# CPU_-_DDR3.net
KiCad netlist of a schematic drawn in Altium Designer
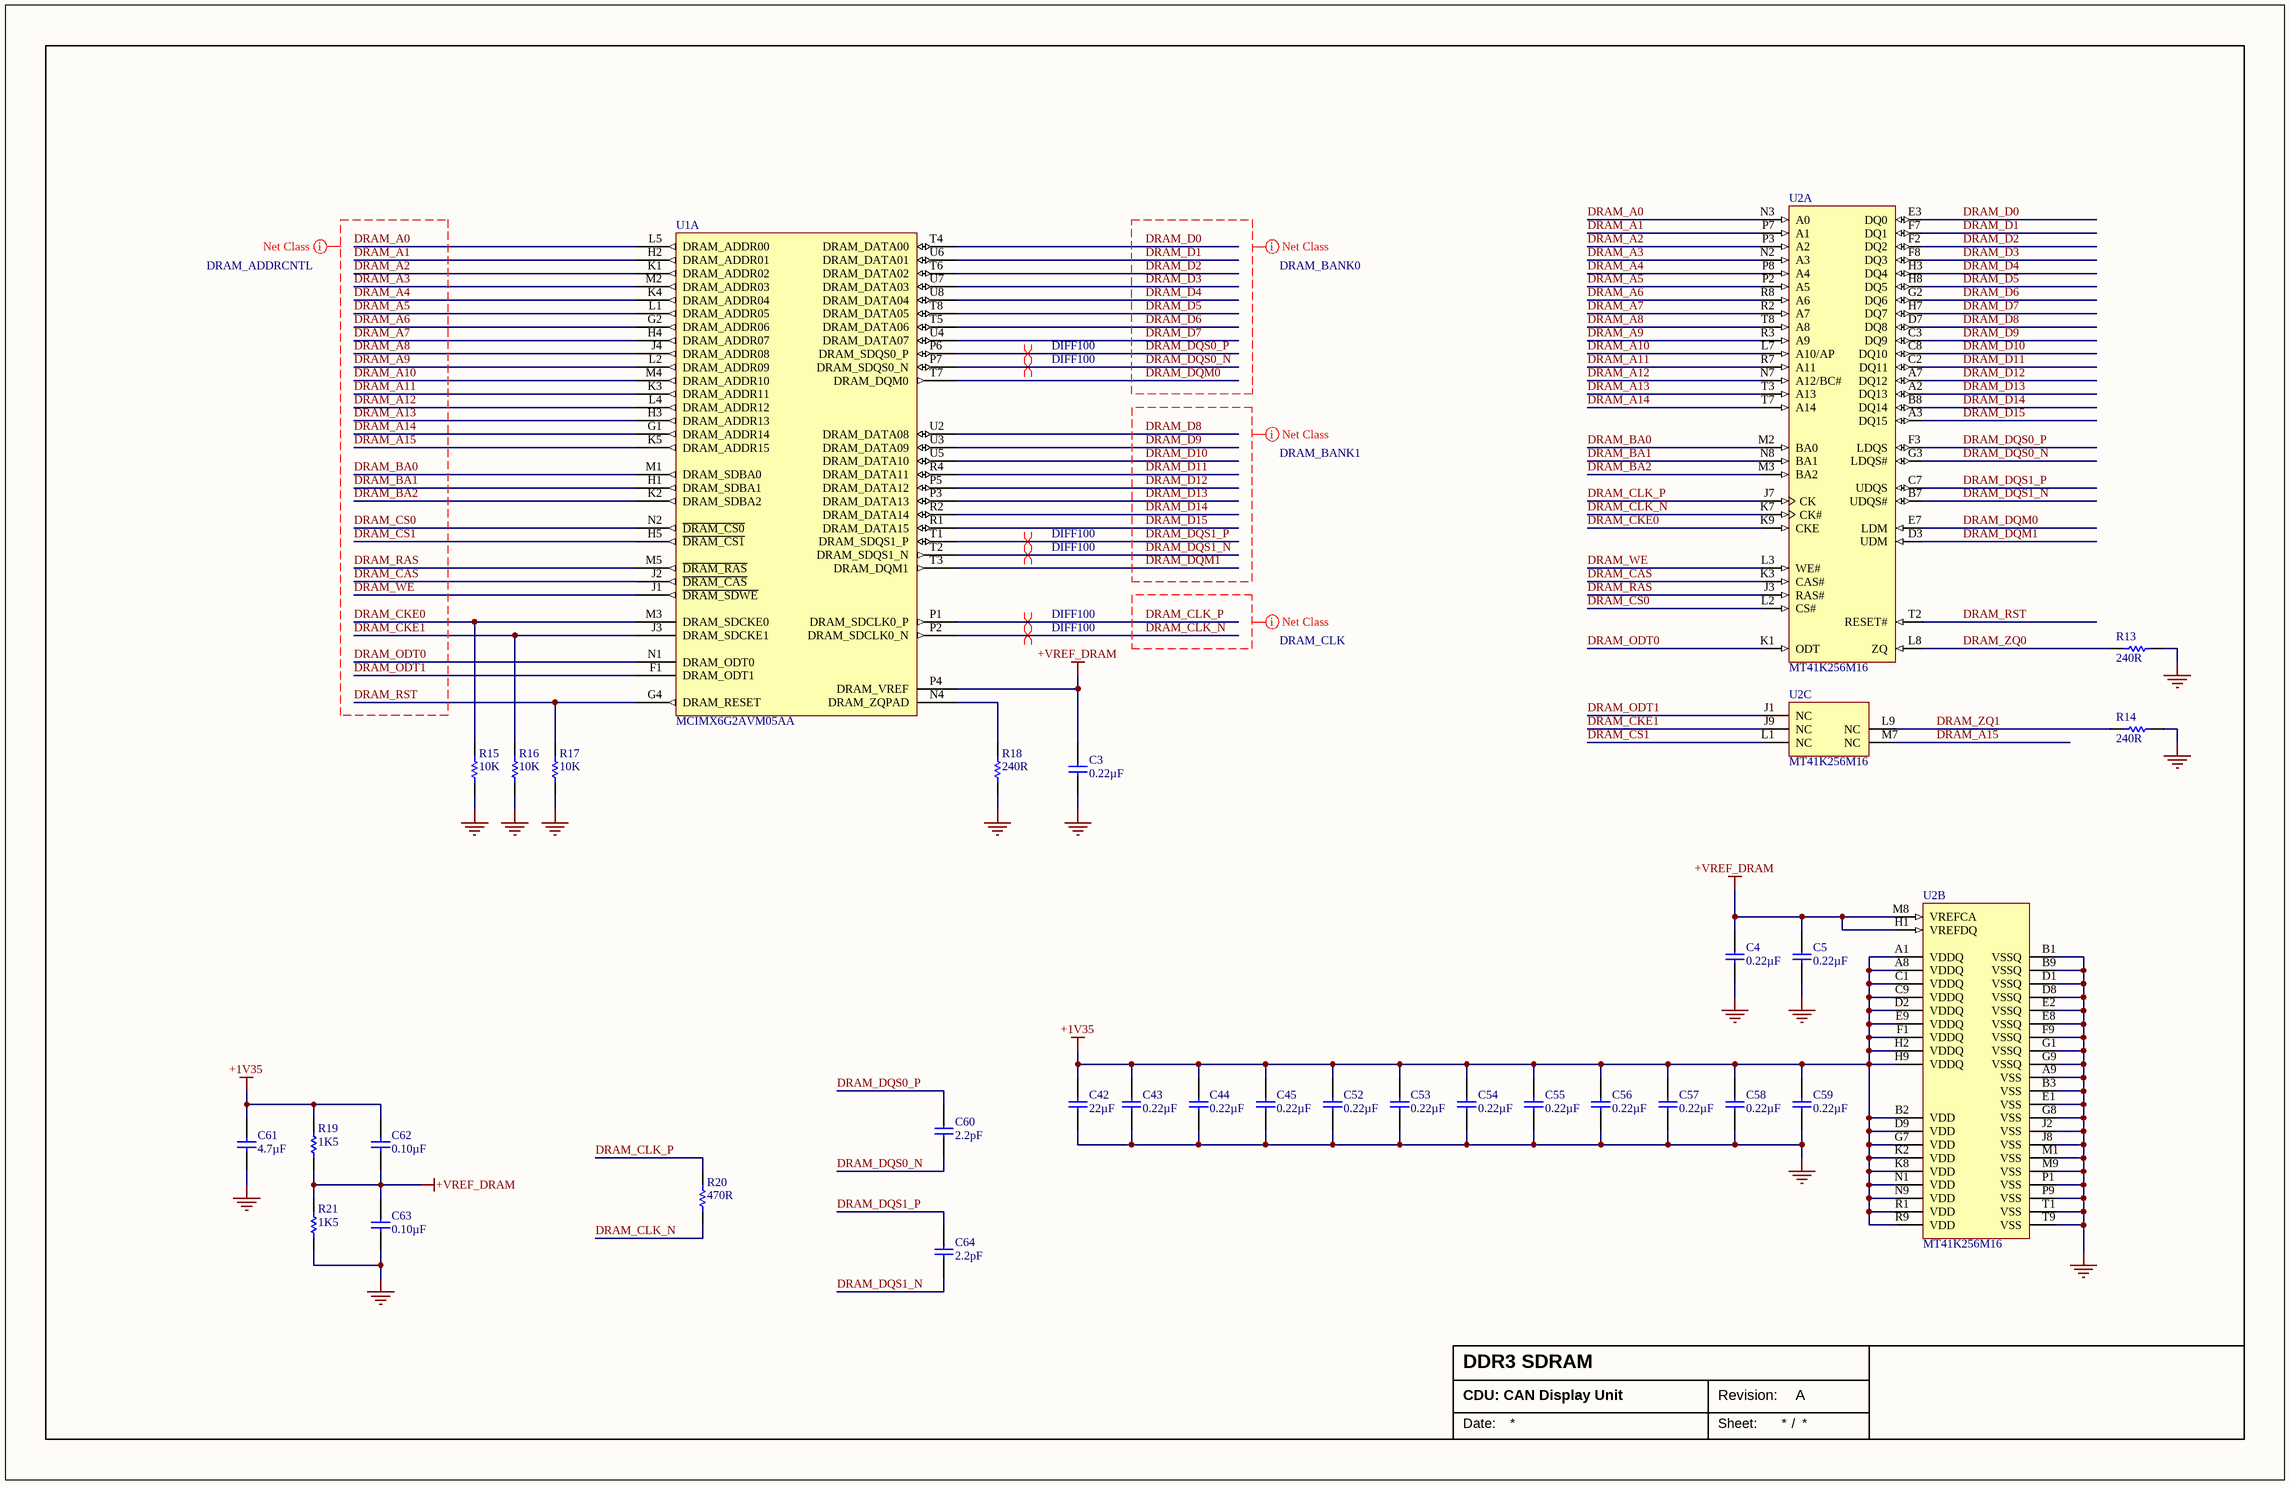
[diagram p0: CPU - DDR3.SchDoc]

(export (version "E")
  (design (tool "Eeschema 10.0.6"))
  (components
    (comp (ref "C3")
      (value "0.22µF")
      (footprint "CAP-0402-M")
      (fields
        (field (name "PART NUMBER") "CC0402KRX7R7BB224")
        (field (name "TOLERANCE") "±10%")
        (field (name "VOLTAGE") "16V")
      )
      (libsource (lib "Capacitors") (part "Capacitor"))
    )
    (comp (ref "C4")
      (value "0.22µF")
      (footprint "CAP-0402-M")
      (fields
        (field (name "PART NUMBER") "CC0402KRX7R7BB224")
        (field (name "TOLERANCE") "±10%")
        (field (name "VOLTAGE") "16V")
      )
      (libsource (lib "Capacitors") (part "Capacitor"))
    )
    (comp (ref "C5")
      (value "0.22µF")
      (footprint "CAP-0402-M")
      (fields
        (field (name "PART NUMBER") "CC0402KRX7R7BB224")
        (field (name "TOLERANCE") "±10%")
        (field (name "VOLTAGE") "16V")
      )
      (libsource (lib "Capacitors") (part "Capacitor"))
    )
    (comp (ref "C42")
      (value "22µF")
      (footprint "CAP-0603-M")
      (fields
        (field (name "PART NUMBER") "CC0603MRX5R6BB226")
        (field (name "TOLERANCE") "±20%")
        (field (name "VOLTAGE") "10V")
      )
      (libsource (lib "Capacitors") (part "Capacitor"))
    )
    (comp (ref "C43")
      (value "0.22µF")
      (footprint "CAP-0402-M")
      (fields
        (field (name "PART NUMBER") "CC0402KRX7R7BB224")
        (field (name "TOLERANCE") "±10%")
        (field (name "VOLTAGE") "16V")
      )
      (libsource (lib "Capacitors") (part "Capacitor"))
    )
    (comp (ref "C44")
      (value "0.22µF")
      (footprint "CAP-0402-M")
      (fields
        (field (name "PART NUMBER") "CC0402KRX7R7BB224")
        (field (name "TOLERANCE") "±10%")
        (field (name "VOLTAGE") "16V")
      )
      (libsource (lib "Capacitors") (part "Capacitor"))
    )
    (comp (ref "C45")
      (value "0.22µF")
      (footprint "CAP-0402-M")
      (fields
        (field (name "PART NUMBER") "CC0402KRX7R7BB224")
        (field (name "TOLERANCE") "±10%")
        (field (name "VOLTAGE") "16V")
      )
      (libsource (lib "Capacitors") (part "Capacitor"))
    )
    (comp (ref "C52")
      (value "0.22µF")
      (footprint "CAP-0402-M")
      (fields
        (field (name "PART NUMBER") "CC0402KRX7R7BB224")
        (field (name "TOLERANCE") "±10%")
        (field (name "VOLTAGE") "16V")
      )
      (libsource (lib "Capacitors") (part "Capacitor"))
    )
    (comp (ref "C53")
      (value "0.22µF")
      (footprint "CAP-0402-M")
      (fields
        (field (name "PART NUMBER") "CC0402KRX7R7BB224")
        (field (name "TOLERANCE") "±10%")
        (field (name "VOLTAGE") "16V")
      )
      (libsource (lib "Capacitors") (part "Capacitor"))
    )
    (comp (ref "C54")
      (value "0.22µF")
      (footprint "CAP-0402-M")
      (fields
        (field (name "PART NUMBER") "CC0402KRX7R7BB224")
        (field (name "TOLERANCE") "±10%")
        (field (name "VOLTAGE") "16V")
      )
      (libsource (lib "Capacitors") (part "Capacitor"))
    )
    (comp (ref "C55")
      (value "0.22µF")
      (footprint "CAP-0402-M")
      (fields
        (field (name "PART NUMBER") "CC0402KRX7R7BB224")
        (field (name "TOLERANCE") "±10%")
        (field (name "VOLTAGE") "16V")
      )
      (libsource (lib "Capacitors") (part "Capacitor"))
    )
    (comp (ref "C56")
      (value "0.22µF")
      (footprint "CAP-0402-M")
      (fields
        (field (name "PART NUMBER") "CC0402KRX7R7BB224")
        (field (name "TOLERANCE") "±10%")
        (field (name "VOLTAGE") "16V")
      )
      (libsource (lib "Capacitors") (part "Capacitor"))
    )
    (comp (ref "C57")
      (value "0.22µF")
      (footprint "CAP-0402-M")
      (fields
        (field (name "PART NUMBER") "CC0402KRX7R7BB224")
        (field (name "TOLERANCE") "±10%")
        (field (name "VOLTAGE") "16V")
      )
      (libsource (lib "Capacitors") (part "Capacitor"))
    )
    (comp (ref "C58")
      (value "0.22µF")
      (footprint "CAP-0402-M")
      (fields
        (field (name "PART NUMBER") "CC0402KRX7R7BB224")
        (field (name "TOLERANCE") "±10%")
        (field (name "VOLTAGE") "16V")
      )
      (libsource (lib "Capacitors") (part "Capacitor"))
    )
    (comp (ref "C59")
      (value "0.22µF")
      (footprint "CAP-0402-M")
      (fields
        (field (name "PART NUMBER") "CC0402KRX7R7BB224")
        (field (name "TOLERANCE") "±10%")
        (field (name "VOLTAGE") "16V")
      )
      (libsource (lib "Capacitors") (part "Capacitor"))
    )
    (comp (ref "C60")
      (value "2.2pF")
      (footprint "CAP-0402-M")
      (fields
        (field (name "PART NUMBER") "CC0402BRNPO9BN2R2")
        (field (name "TOLERANCE") "±0.1pF")
        (field (name "VOLTAGE") "50V")
      )
      (libsource (lib "Capacitors") (part "Capacitor"))
    )
    (comp (ref "C61")
      (value "4.7µF")
      (footprint "CAP-0603-M")
      (fields
        (field (name "PART NUMBER") "CC0603KRX5R6BB475")
        (field (name "TOLERANCE") "±10%")
        (field (name "VOLTAGE") "10V")
      )
      (libsource (lib "Capacitors") (part "Capacitor"))
    )
    (comp (ref "C62")
      (value "0.10µF")
      (footprint "CAP-0402-M")
      (fields
        (field (name "PART NUMBER") "CC0402KRX7R8BB104")
        (field (name "TOLERANCE") "±10%")
        (field (name "VOLTAGE") "25V")
      )
      (libsource (lib "Capacitors") (part "Capacitor"))
    )
    (comp (ref "C63")
      (value "0.10µF")
      (footprint "CAP-0402-M")
      (fields
        (field (name "PART NUMBER") "CC0402KRX7R8BB104")
        (field (name "TOLERANCE") "±10%")
        (field (name "VOLTAGE") "25V")
      )
      (libsource (lib "Capacitors") (part "Capacitor"))
    )
    (comp (ref "C64")
      (value "2.2pF")
      (footprint "CAP-0402-M")
      (fields
        (field (name "PART NUMBER") "CC0402BRNPO9BN2R2")
        (field (name "TOLERANCE") "±0.1pF")
        (field (name "VOLTAGE") "50V")
      )
      (libsource (lib "Capacitors") (part "Capacitor"))
    )
    (comp (ref "R13")
      (value "240R")
      (footprint "RES-0402-M")
      (fields
        (field (name "PART NUMBER") "RC0402FR-07240RL")
        (field (name "TOLERANCE") "1%")
        (field (name "POWER") "1/16W")
      )
      (libsource (lib "Resistors") (part "Resistor"))
    )
    (comp (ref "R14")
      (value "240R")
      (footprint "RES-0402-M")
      (fields
        (field (name "PART NUMBER") "RC0402FR-07240RL")
        (field (name "TOLERANCE") "1%")
        (field (name "POWER") "1/16W")
      )
      (libsource (lib "Resistors") (part "Resistor"))
    )
    (comp (ref "R15")
      (value "10K")
      (footprint "RES-0603-M")
      (fields
        (field (name "PART NUMBER") "RC0603FR-0710KL")
        (field (name "TOLERANCE") "1%")
        (field (name "POWER") "1/10 W")
      )
      (libsource (lib "Resistors") (part "Resistor"))
    )
    (comp (ref "R16")
      (value "10K")
      (footprint "RES-0603-M")
      (fields
        (field (name "PART NUMBER") "RC0603FR-0710KL")
        (field (name "TOLERANCE") "1%")
        (field (name "POWER") "1/10 W")
      )
      (libsource (lib "Resistors") (part "Resistor"))
    )
    (comp (ref "R17")
      (value "10K")
      (footprint "RES-0603-M")
      (fields
        (field (name "PART NUMBER") "RC0603FR-0710KL")
        (field (name "TOLERANCE") "1%")
        (field (name "POWER") "1/10 W")
      )
      (libsource (lib "Resistors") (part "Resistor"))
    )
    (comp (ref "R18")
      (value "240R")
      (footprint "RES-0402-M")
      (fields
        (field (name "PART NUMBER") "RC0402FR-07240RL")
        (field (name "TOLERANCE") "1%")
        (field (name "POWER") "1/16W")
      )
      (libsource (lib "Resistors") (part "Resistor"))
    )
    (comp (ref "R19")
      (value "1K5")
      (footprint "RES-0603-M")
      (fields
        (field (name "PART NUMBER") "RC0603FR-071K5L")
        (field (name "TOLERANCE") "1%")
        (field (name "POWER") "1/10 W")
      )
      (libsource (lib "Resistors") (part "Resistor"))
    )
    (comp (ref "R20")
      (value "470R")
      (footprint "RES-0402-M")
      (fields
        (field (name "PART NUMBER") "RC0402FR-07470RL")
        (field (name "TOLERANCE") "1%")
        (field (name "POWER") "1/16W")
      )
      (libsource (lib "Resistors") (part "Resistor"))
    )
    (comp (ref "R21")
      (value "1K5")
      (footprint "RES-0603-M")
      (fields
        (field (name "PART NUMBER") "RC0603FR-071K5L")
        (field (name "TOLERANCE") "1%")
        (field (name "POWER") "1/10 W")
      )
      (libsource (lib "Resistors") (part "Resistor"))
    )
    (comp (ref "U1")
      (value "MCIMX6G2AVM05AA")
      (footprint "BGA289C80P17X17_1400X1400X132")
      (libsource (lib "Hub-UV17") (part "MCIMX6G2AVM05AA"))
    )
    (comp (ref "U2")
      (value "MT41K256M16")
      (footprint "MICT-HA-96")
      (libsource (lib "Hub-UV17") (part "MT41K256M16"))
    )
  )
  (nets
    (net (code "1") (name "+1V35") (class "Default")
      (node (ref "C42") (pin "2") (pinfunction "2_2") (pintype "passive"))
      (node (ref "C43") (pin "1") (pinfunction "1_1") (pintype "passive"))
      (node (ref "C44") (pin "1") (pinfunction "1_1") (pintype "passive"))
      (node (ref "C45") (pin "1") (pinfunction "1_1") (pintype "passive"))
      (node (ref "C52") (pin "1") (pinfunction "1_1") (pintype "passive"))
      (node (ref "C53") (pin "1") (pinfunction "1_1") (pintype "passive"))
      (node (ref "C54") (pin "1") (pinfunction "1_1") (pintype "passive"))
      (node (ref "C55") (pin "1") (pinfunction "1_1") (pintype "passive"))
      (node (ref "C56") (pin "1") (pinfunction "1_1") (pintype "passive"))
      (node (ref "C57") (pin "1") (pinfunction "1_1") (pintype "passive"))
      (node (ref "C58") (pin "1") (pinfunction "1_1") (pintype "passive"))
      (node (ref "C59") (pin "1") (pinfunction "1_1") (pintype "passive"))
      (node (ref "C61") (pin "2") (pinfunction "2_2") (pintype "passive"))
      (node (ref "C62") (pin "2") (pinfunction "2_2") (pintype "passive"))
      (node (ref "R19") (pin "2") (pinfunction "2_2") (pintype "passive"))
      (node (ref "U2") (pin "A1") (pinfunction "VDDQ_A1") (pintype "power_in"))
      (node (ref "U2") (pin "A8") (pinfunction "VDDQ_A8") (pintype "power_in"))
      (node (ref "U2") (pin "B2") (pinfunction "VDD_B2") (pintype "power_in"))
      (node (ref "U2") (pin "C1") (pinfunction "VDDQ_C1") (pintype "power_in"))
      (node (ref "U2") (pin "C9") (pinfunction "VDDQ_C9") (pintype "power_in"))
      (node (ref "U2") (pin "D2") (pinfunction "VDDQ_D2") (pintype "power_in"))
      (node (ref "U2") (pin "D9") (pinfunction "VDD_D9") (pintype "power_in"))
      (node (ref "U2") (pin "E9") (pinfunction "VDDQ_E9") (pintype "power_in"))
      (node (ref "U2") (pin "F1") (pinfunction "VDDQ_F1") (pintype "power_in"))
      (node (ref "U2") (pin "G7") (pinfunction "VDD_G7") (pintype "power_in"))
      (node (ref "U2") (pin "H2") (pinfunction "VDDQ_H2") (pintype "power_in"))
      (node (ref "U2") (pin "H9") (pinfunction "VDDQ_H9") (pintype "power_in"))
      (node (ref "U2") (pin "K2") (pinfunction "VDD_K2") (pintype "power_in"))
      (node (ref "U2") (pin "K8") (pinfunction "VDD_K8") (pintype "power_in"))
      (node (ref "U2") (pin "N1") (pinfunction "VDD_N1") (pintype "power_in"))
      (node (ref "U2") (pin "N9") (pinfunction "VDD_N9") (pintype "power_in"))
      (node (ref "U2") (pin "R1") (pinfunction "VDD_R1") (pintype "power_in"))
      (node (ref "U2") (pin "R9") (pinfunction "VDD_R9") (pintype "power_in"))
    )
    (net (code "2") (name "+VREF_DRAM") (class "Default")
      (node (ref "C3") (pin "1") (pinfunction "1_1") (pintype "passive"))
      (node (ref "C4") (pin "1") (pinfunction "1_1") (pintype "passive"))
      (node (ref "C5") (pin "1") (pinfunction "1_1") (pintype "passive"))
      (node (ref "C62") (pin "1") (pinfunction "1_1") (pintype "passive"))
      (node (ref "C63") (pin "2") (pinfunction "2_2") (pintype "passive"))
      (node (ref "R19") (pin "1") (pinfunction "1_1") (pintype "passive"))
      (node (ref "R21") (pin "2") (pinfunction "2_2") (pintype "passive"))
      (node (ref "U1") (pin "P4") (pinfunction "DRAM_VREF_P4") (pintype "power_in"))
      (node (ref "U2") (pin "H1") (pinfunction "VREFDQ_H1") (pintype "input"))
      (node (ref "U2") (pin "M8") (pinfunction "VREFCA_M8") (pintype "input"))
    )
    (net (code "3") (name "/DRAM_A0") (class "Default")
      (node (ref "U1") (pin "L5") (pinfunction "DRAM_ADDR00_L5") (pintype "output"))
      (node (ref "U2") (pin "N3") (pinfunction "A0_N3") (pintype "input"))
    )
    (net (code "4") (name "/DRAM_A1") (class "Default")
      (node (ref "U1") (pin "H2") (pinfunction "DRAM_ADDR01_H2") (pintype "output"))
      (node (ref "U2") (pin "P7") (pinfunction "A1_P7") (pintype "input"))
    )
    (net (code "5") (name "/DRAM_A2") (class "Default")
      (node (ref "U1") (pin "K1") (pinfunction "DRAM_ADDR02_K1") (pintype "output"))
      (node (ref "U2") (pin "P3") (pinfunction "A2_P3") (pintype "input"))
    )
    (net (code "6") (name "/DRAM_A3") (class "Default")
      (node (ref "U1") (pin "M2") (pinfunction "DRAM_ADDR03_M2") (pintype "output"))
      (node (ref "U2") (pin "N2") (pinfunction "A3_N2") (pintype "input"))
    )
    (net (code "7") (name "/DRAM_A4") (class "Default")
      (node (ref "U1") (pin "K4") (pinfunction "DRAM_ADDR04_K4") (pintype "output"))
      (node (ref "U2") (pin "P8") (pinfunction "A4_P8") (pintype "input"))
    )
    (net (code "8") (name "/DRAM_A5") (class "Default")
      (node (ref "U1") (pin "L1") (pinfunction "DRAM_ADDR05_L1") (pintype "output"))
      (node (ref "U2") (pin "P2") (pinfunction "A5_P2") (pintype "input"))
    )
    (net (code "9") (name "/DRAM_A6") (class "Default")
      (node (ref "U1") (pin "G2") (pinfunction "DRAM_ADDR06_G2") (pintype "output"))
      (node (ref "U2") (pin "R8") (pinfunction "A6_R8") (pintype "input"))
    )
    (net (code "10") (name "/DRAM_A7") (class "Default")
      (node (ref "U1") (pin "H4") (pinfunction "DRAM_ADDR07_H4") (pintype "output"))
      (node (ref "U2") (pin "R2") (pinfunction "A7_R2") (pintype "input"))
    )
    (net (code "11") (name "/DRAM_A8") (class "Default")
      (node (ref "U1") (pin "J4") (pinfunction "DRAM_ADDR08_J4") (pintype "output"))
      (node (ref "U2") (pin "T8") (pinfunction "A8_T8") (pintype "input"))
    )
    (net (code "12") (name "/DRAM_A9") (class "Default")
      (node (ref "U1") (pin "L2") (pinfunction "DRAM_ADDR09_L2") (pintype "output"))
      (node (ref "U2") (pin "R3") (pinfunction "A9_R3") (pintype "input"))
    )
    (net (code "13") (name "/DRAM_A10") (class "Default")
      (node (ref "U1") (pin "M4") (pinfunction "DRAM_ADDR10_M4") (pintype "output"))
      (node (ref "U2") (pin "L7") (pinfunction "A10/AP_L7") (pintype "input"))
    )
    (net (code "14") (name "/DRAM_A11") (class "Default")
      (node (ref "U1") (pin "K3") (pinfunction "DRAM_ADDR11_K3") (pintype "output"))
      (node (ref "U2") (pin "R7") (pinfunction "A11_R7") (pintype "input"))
    )
    (net (code "15") (name "/DRAM_A12") (class "Default")
      (node (ref "U1") (pin "L4") (pinfunction "DRAM_ADDR12_L4") (pintype "output"))
      (node (ref "U2") (pin "N7") (pinfunction "A12/BC#_N7") (pintype "input"))
    )
    (net (code "16") (name "/DRAM_A13") (class "Default")
      (node (ref "U1") (pin "H3") (pinfunction "DRAM_ADDR13_H3") (pintype "output"))
      (node (ref "U2") (pin "T3") (pinfunction "A13_T3") (pintype "input"))
    )
    (net (code "17") (name "/DRAM_A14") (class "Default")
      (node (ref "U1") (pin "G1") (pinfunction "DRAM_ADDR14_G1") (pintype "output"))
      (node (ref "U2") (pin "T7") (pinfunction "A14_T7") (pintype "input"))
    )
    (net (code "18") (name "/DRAM_A15") (class "Default")
      (node (ref "U1") (pin "K5") (pinfunction "DRAM_ADDR15_K5") (pintype "output"))
      (node (ref "U2") (pin "M7") (pinfunction "NC_M7") (pintype "passive"))
    )
    (net (code "19") (name "/DRAM_BA0") (class "Default")
      (node (ref "U1") (pin "M1") (pinfunction "DRAM_SDBA0_M1") (pintype "output"))
      (node (ref "U2") (pin "M2") (pinfunction "BA0_M2") (pintype "input"))
    )
    (net (code "20") (name "/DRAM_BA1") (class "Default")
      (node (ref "U1") (pin "H1") (pinfunction "DRAM_SDBA1_H1") (pintype "output"))
      (node (ref "U2") (pin "N8") (pinfunction "BA1_N8") (pintype "input"))
    )
    (net (code "21") (name "/DRAM_BA2") (class "Default")
      (node (ref "U1") (pin "K2") (pinfunction "DRAM_SDBA2_K2") (pintype "output"))
      (node (ref "U2") (pin "M3") (pinfunction "BA2_M3") (pintype "input"))
    )
    (net (code "22") (name "/DRAM_CAS") (class "Default")
      (node (ref "U1") (pin "J2") (pinfunction "~{DRAM_CAS}_J2") (pintype "output"))
      (node (ref "U2") (pin "K3") (pinfunction "CAS#_K3") (pintype "input"))
    )
    (net (code "23") (name "/DRAM_CKE0") (class "Default")
      (node (ref "R15") (pin "2") (pinfunction "2_2") (pintype "passive"))
      (node (ref "U1") (pin "M3") (pinfunction "DRAM_SDCKE0_M3") (pintype "passive"))
      (node (ref "U2") (pin "K9") (pinfunction "CKE_K9") (pintype "input"))
    )
    (net (code "24") (name "/DRAM_CKE1") (class "Default")
      (node (ref "R16") (pin "2") (pinfunction "2_2") (pintype "passive"))
      (node (ref "U1") (pin "J3") (pinfunction "DRAM_SDCKE1_J3") (pintype "passive"))
      (node (ref "U2") (pin "J9") (pinfunction "NC_J9") (pintype "passive"))
    )
    (net (code "25") (name "/DRAM_CLK_N") (class "Default")
      (node (ref "R20") (pin "1") (pinfunction "1_1") (pintype "passive"))
      (node (ref "U1") (pin "P2") (pinfunction "DRAM_SDCLK0_N_P2") (pintype "output"))
      (node (ref "U2") (pin "K7") (pinfunction "CK#_K7") (pintype "input"))
    )
    (net (code "26") (name "/DRAM_CLK_P") (class "Default")
      (node (ref "R20") (pin "2") (pinfunction "2_2") (pintype "passive"))
      (node (ref "U1") (pin "P1") (pinfunction "DRAM_SDCLK0_P_P1") (pintype "output"))
      (node (ref "U2") (pin "J7") (pinfunction "CK_J7") (pintype "input"))
    )
    (net (code "27") (name "/DRAM_CS0") (class "Default")
      (node (ref "U1") (pin "N2") (pinfunction "~{DRAM_CS0}_N2") (pintype "output"))
      (node (ref "U2") (pin "L2") (pinfunction "CS#_L2") (pintype "input"))
    )
    (net (code "28") (name "/DRAM_CS1") (class "Default")
      (node (ref "U1") (pin "H5") (pinfunction "~{DRAM_CS1}_H5") (pintype "output"))
      (node (ref "U2") (pin "L1") (pinfunction "NC_L1") (pintype "passive"))
    )
    (net (code "29") (name "/DRAM_D0") (class "Default")
      (node (ref "U1") (pin "T4") (pinfunction "DRAM_DATA00_T4") (pintype "bidirectional"))
      (node (ref "U2") (pin "E3") (pinfunction "DQ0_E3") (pintype "bidirectional"))
    )
    (net (code "30") (name "/DRAM_D1") (class "Default")
      (node (ref "U1") (pin "U6") (pinfunction "DRAM_DATA01_U6") (pintype "bidirectional"))
      (node (ref "U2") (pin "F7") (pinfunction "DQ1_F7") (pintype "bidirectional"))
    )
    (net (code "31") (name "/DRAM_D2") (class "Default")
      (node (ref "U1") (pin "T6") (pinfunction "DRAM_DATA02_T6") (pintype "bidirectional"))
      (node (ref "U2") (pin "F2") (pinfunction "DQ2_F2") (pintype "bidirectional"))
    )
    (net (code "32") (name "/DRAM_D3") (class "Default")
      (node (ref "U1") (pin "U7") (pinfunction "DRAM_DATA03_U7") (pintype "bidirectional"))
      (node (ref "U2") (pin "F8") (pinfunction "DQ3_F8") (pintype "bidirectional"))
    )
    (net (code "33") (name "/DRAM_D4") (class "Default")
      (node (ref "U1") (pin "U8") (pinfunction "DRAM_DATA04_U8") (pintype "bidirectional"))
      (node (ref "U2") (pin "H3") (pinfunction "DQ4_H3") (pintype "bidirectional"))
    )
    (net (code "34") (name "/DRAM_D5") (class "Default")
      (node (ref "U1") (pin "T8") (pinfunction "DRAM_DATA05_T8") (pintype "bidirectional"))
      (node (ref "U2") (pin "H8") (pinfunction "DQ5_H8") (pintype "bidirectional"))
    )
    (net (code "35") (name "/DRAM_D6") (class "Default")
      (node (ref "U1") (pin "T5") (pinfunction "DRAM_DATA06_T5") (pintype "bidirectional"))
      (node (ref "U2") (pin "G2") (pinfunction "DQ6_G2") (pintype "bidirectional"))
    )
    (net (code "36") (name "/DRAM_D7") (class "Default")
      (node (ref "U1") (pin "U4") (pinfunction "DRAM_DATA07_U4") (pintype "bidirectional"))
      (node (ref "U2") (pin "H7") (pinfunction "DQ7_H7") (pintype "bidirectional"))
    )
    (net (code "37") (name "/DRAM_D8") (class "Default")
      (node (ref "U1") (pin "U2") (pinfunction "DRAM_DATA08_U2") (pintype "bidirectional"))
      (node (ref "U2") (pin "D7") (pinfunction "DQ8_D7") (pintype "bidirectional"))
    )
    (net (code "38") (name "/DRAM_D9") (class "Default")
      (node (ref "U1") (pin "U3") (pinfunction "DRAM_DATA09_U3") (pintype "bidirectional"))
      (node (ref "U2") (pin "C3") (pinfunction "DQ9_C3") (pintype "bidirectional"))
    )
    (net (code "39") (name "/DRAM_D10") (class "Default")
      (node (ref "U1") (pin "U5") (pinfunction "DRAM_DATA10_U5") (pintype "bidirectional"))
      (node (ref "U2") (pin "C8") (pinfunction "DQ10_C8") (pintype "bidirectional"))
    )
    (net (code "40") (name "/DRAM_D11") (class "Default")
      (node (ref "U1") (pin "R4") (pinfunction "DRAM_DATA11_R4") (pintype "bidirectional"))
      (node (ref "U2") (pin "C2") (pinfunction "DQ11_C2") (pintype "bidirectional"))
    )
    (net (code "41") (name "/DRAM_D12") (class "Default")
      (node (ref "U1") (pin "P5") (pinfunction "DRAM_DATA12_P5") (pintype "bidirectional"))
      (node (ref "U2") (pin "A7") (pinfunction "DQ12_A7") (pintype "bidirectional"))
    )
    (net (code "42") (name "/DRAM_D13") (class "Default")
      (node (ref "U1") (pin "P3") (pinfunction "DRAM_DATA13_P3") (pintype "bidirectional"))
      (node (ref "U2") (pin "A2") (pinfunction "DQ13_A2") (pintype "bidirectional"))
    )
    (net (code "43") (name "/DRAM_D14") (class "Default")
      (node (ref "U1") (pin "R2") (pinfunction "DRAM_DATA14_R2") (pintype "bidirectional"))
      (node (ref "U2") (pin "B8") (pinfunction "DQ14_B8") (pintype "bidirectional"))
    )
    (net (code "44") (name "/DRAM_D15") (class "Default")
      (node (ref "U1") (pin "R1") (pinfunction "DRAM_DATA15_R1") (pintype "bidirectional"))
      (node (ref "U2") (pin "A3") (pinfunction "DQ15_A3") (pintype "bidirectional"))
    )
    (net (code "45") (name "/DRAM_DQM0") (class "Default")
      (node (ref "U1") (pin "T7") (pinfunction "DRAM_DQM0_T7") (pintype "output"))
      (node (ref "U2") (pin "E7") (pinfunction "LDM_E7") (pintype "input"))
    )
    (net (code "46") (name "/DRAM_DQM1") (class "Default")
      (node (ref "U1") (pin "T3") (pinfunction "DRAM_DQM1_T3") (pintype "output"))
      (node (ref "U2") (pin "D3") (pinfunction "UDM_D3") (pintype "input"))
    )
    (net (code "47") (name "/DRAM_DQS0_N") (class "Default")
      (node (ref "C60") (pin "2") (pinfunction "2_2") (pintype "passive"))
      (node (ref "U1") (pin "P7") (pinfunction "DRAM_SDQS0_N_P7") (pintype "bidirectional"))
      (node (ref "U2") (pin "G3") (pinfunction "LDQS#_G3") (pintype "bidirectional"))
    )
    (net (code "48") (name "/DRAM_DQS0_P") (class "Default")
      (node (ref "C60") (pin "1") (pinfunction "1_1") (pintype "passive"))
      (node (ref "U1") (pin "P6") (pinfunction "DRAM_SDQS0_P_P6") (pintype "bidirectional"))
      (node (ref "U2") (pin "F3") (pinfunction "LDQS_F3") (pintype "bidirectional"))
    )
    (net (code "49") (name "/DRAM_DQS1_N") (class "Default")
      (node (ref "C64") (pin "2") (pinfunction "2_2") (pintype "passive"))
      (node (ref "U1") (pin "T2") (pinfunction "DRAM_SDQS1_N_T2") (pintype "output"))
      (node (ref "U2") (pin "B7") (pinfunction "UDQS#_B7") (pintype "bidirectional"))
    )
    (net (code "50") (name "/DRAM_DQS1_P") (class "Default")
      (node (ref "C64") (pin "1") (pinfunction "1_1") (pintype "passive"))
      (node (ref "U1") (pin "T1") (pinfunction "DRAM_SDQS1_P_T1") (pintype "bidirectional"))
      (node (ref "U2") (pin "C7") (pinfunction "UDQS_C7") (pintype "bidirectional"))
    )
    (net (code "51") (name "/DRAM_ODT0") (class "Default")
      (node (ref "U1") (pin "N1") (pinfunction "DRAM_ODT0_N1") (pintype "passive"))
      (node (ref "U2") (pin "K1") (pinfunction "ODT_K1") (pintype "input"))
    )
    (net (code "52") (name "/DRAM_ODT1") (class "Default")
      (node (ref "U1") (pin "F1") (pinfunction "DRAM_ODT1_F1") (pintype "passive"))
      (node (ref "U2") (pin "J1") (pinfunction "NC_J1") (pintype "passive"))
    )
    (net (code "53") (name "/DRAM_RAS") (class "Default")
      (node (ref "U1") (pin "M5") (pinfunction "~{DRAM_RAS}_M5") (pintype "output"))
      (node (ref "U2") (pin "J3") (pinfunction "RAS#_J3") (pintype "input"))
    )
    (net (code "54") (name "/DRAM_RST") (class "Default")
      (node (ref "R17") (pin "2") (pinfunction "2_2") (pintype "passive"))
      (node (ref "U1") (pin "G4") (pinfunction "DRAM_RESET_G4") (pintype "output"))
      (node (ref "U2") (pin "T2") (pinfunction "RESET#_T2") (pintype "input"))
    )
    (net (code "55") (name "/DRAM_WE") (class "Default")
      (node (ref "U1") (pin "J1") (pinfunction "~{DRAM_SDWE}_J1") (pintype "output"))
      (node (ref "U2") (pin "L3") (pinfunction "WE#_L3") (pintype "input"))
    )
    (net (code "56") (name "/DRAM_ZQ0") (class "Default")
      (node (ref "R13") (pin "2") (pinfunction "2_2") (pintype "passive"))
      (node (ref "U2") (pin "L8") (pinfunction "ZQ_L8") (pintype "input"))
    )
    (net (code "57") (name "/DRAM_ZQ1") (class "Default")
      (node (ref "R14") (pin "2") (pinfunction "2_2") (pintype "passive"))
      (node (ref "U2") (pin "L9") (pinfunction "NC_L9") (pintype "passive"))
    )
    (net (code "58") (name "GND") (class "Default")
      (node (ref "C3") (pin "2") (pinfunction "2_2") (pintype "passive"))
      (node (ref "C4") (pin "2") (pinfunction "2_2") (pintype "passive"))
      (node (ref "C42") (pin "1") (pinfunction "1_1") (pintype "passive"))
      (node (ref "C43") (pin "2") (pinfunction "2_2") (pintype "passive"))
      (node (ref "C44") (pin "2") (pinfunction "2_2") (pintype "passive"))
      (node (ref "C45") (pin "2") (pinfunction "2_2") (pintype "passive"))
      (node (ref "C5") (pin "2") (pinfunction "2_2") (pintype "passive"))
      (node (ref "C52") (pin "2") (pinfunction "2_2") (pintype "passive"))
      (node (ref "C53") (pin "2") (pinfunction "2_2") (pintype "passive"))
      (node (ref "C54") (pin "2") (pinfunction "2_2") (pintype "passive"))
      (node (ref "C55") (pin "2") (pinfunction "2_2") (pintype "passive"))
      (node (ref "C56") (pin "2") (pinfunction "2_2") (pintype "passive"))
      (node (ref "C57") (pin "2") (pinfunction "2_2") (pintype "passive"))
      (node (ref "C58") (pin "2") (pinfunction "2_2") (pintype "passive"))
      (node (ref "C59") (pin "2") (pinfunction "2_2") (pintype "passive"))
      (node (ref "C61") (pin "1") (pinfunction "1_1") (pintype "passive"))
      (node (ref "C63") (pin "1") (pinfunction "1_1") (pintype "passive"))
      (node (ref "R13") (pin "1") (pinfunction "1_1") (pintype "passive"))
      (node (ref "R14") (pin "1") (pinfunction "1_1") (pintype "passive"))
      (node (ref "R15") (pin "1") (pinfunction "1_1") (pintype "passive"))
      (node (ref "R16") (pin "1") (pinfunction "1_1") (pintype "passive"))
      (node (ref "R17") (pin "1") (pinfunction "1_1") (pintype "passive"))
      (node (ref "R18") (pin "1") (pinfunction "1_1") (pintype "passive"))
      (node (ref "R21") (pin "1") (pinfunction "1_1") (pintype "passive"))
      (node (ref "U2") (pin "A9") (pinfunction "VSS_A9") (pintype "power_in"))
      (node (ref "U2") (pin "B1") (pinfunction "VSSQ_B1") (pintype "power_in"))
      (node (ref "U2") (pin "B3") (pinfunction "VSS_B3") (pintype "power_in"))
      (node (ref "U2") (pin "B9") (pinfunction "VSSQ_B9") (pintype "power_in"))
      (node (ref "U2") (pin "D1") (pinfunction "VSSQ_D1") (pintype "power_in"))
      (node (ref "U2") (pin "D8") (pinfunction "VSSQ_D8") (pintype "power_in"))
      (node (ref "U2") (pin "E1") (pinfunction "VSS_E1") (pintype "power_in"))
      (node (ref "U2") (pin "E2") (pinfunction "VSSQ_E2") (pintype "power_in"))
      (node (ref "U2") (pin "E8") (pinfunction "VSSQ_E8") (pintype "power_in"))
      (node (ref "U2") (pin "F9") (pinfunction "VSSQ_F9") (pintype "power_in"))
      (node (ref "U2") (pin "G1") (pinfunction "VSSQ_G1") (pintype "power_in"))
      (node (ref "U2") (pin "G8") (pinfunction "VSS_G8") (pintype "power_in"))
      (node (ref "U2") (pin "G9") (pinfunction "VSSQ_G9") (pintype "power_in"))
      (node (ref "U2") (pin "J2") (pinfunction "VSS_J2") (pintype "power_in"))
      (node (ref "U2") (pin "J8") (pinfunction "VSS_J8") (pintype "power_in"))
      (node (ref "U2") (pin "M1") (pinfunction "VSS_M1") (pintype "power_in"))
      (node (ref "U2") (pin "M9") (pinfunction "VSS_M9") (pintype "power_in"))
      (node (ref "U2") (pin "P1") (pinfunction "VSS_P1") (pintype "power_in"))
      (node (ref "U2") (pin "P9") (pinfunction "VSS_P9") (pintype "power_in"))
      (node (ref "U2") (pin "T1") (pinfunction "VSS_T1") (pintype "power_in"))
      (node (ref "U2") (pin "T9") (pinfunction "VSS_T9") (pintype "power_in"))
    )
    (net (code "59") (name "Net-(U1A-DRAM_ZQPAD)") (class "Default")
      (node (ref "R18") (pin "2") (pinfunction "2_2") (pintype "passive"))
      (node (ref "U1") (pin "N4") (pinfunction "DRAM_ZQPAD_N4") (pintype "passive"))
    )
  )
)
